# Smart-window_v1_1.net
KiCad netlist of a schematic drawn in EAGLE
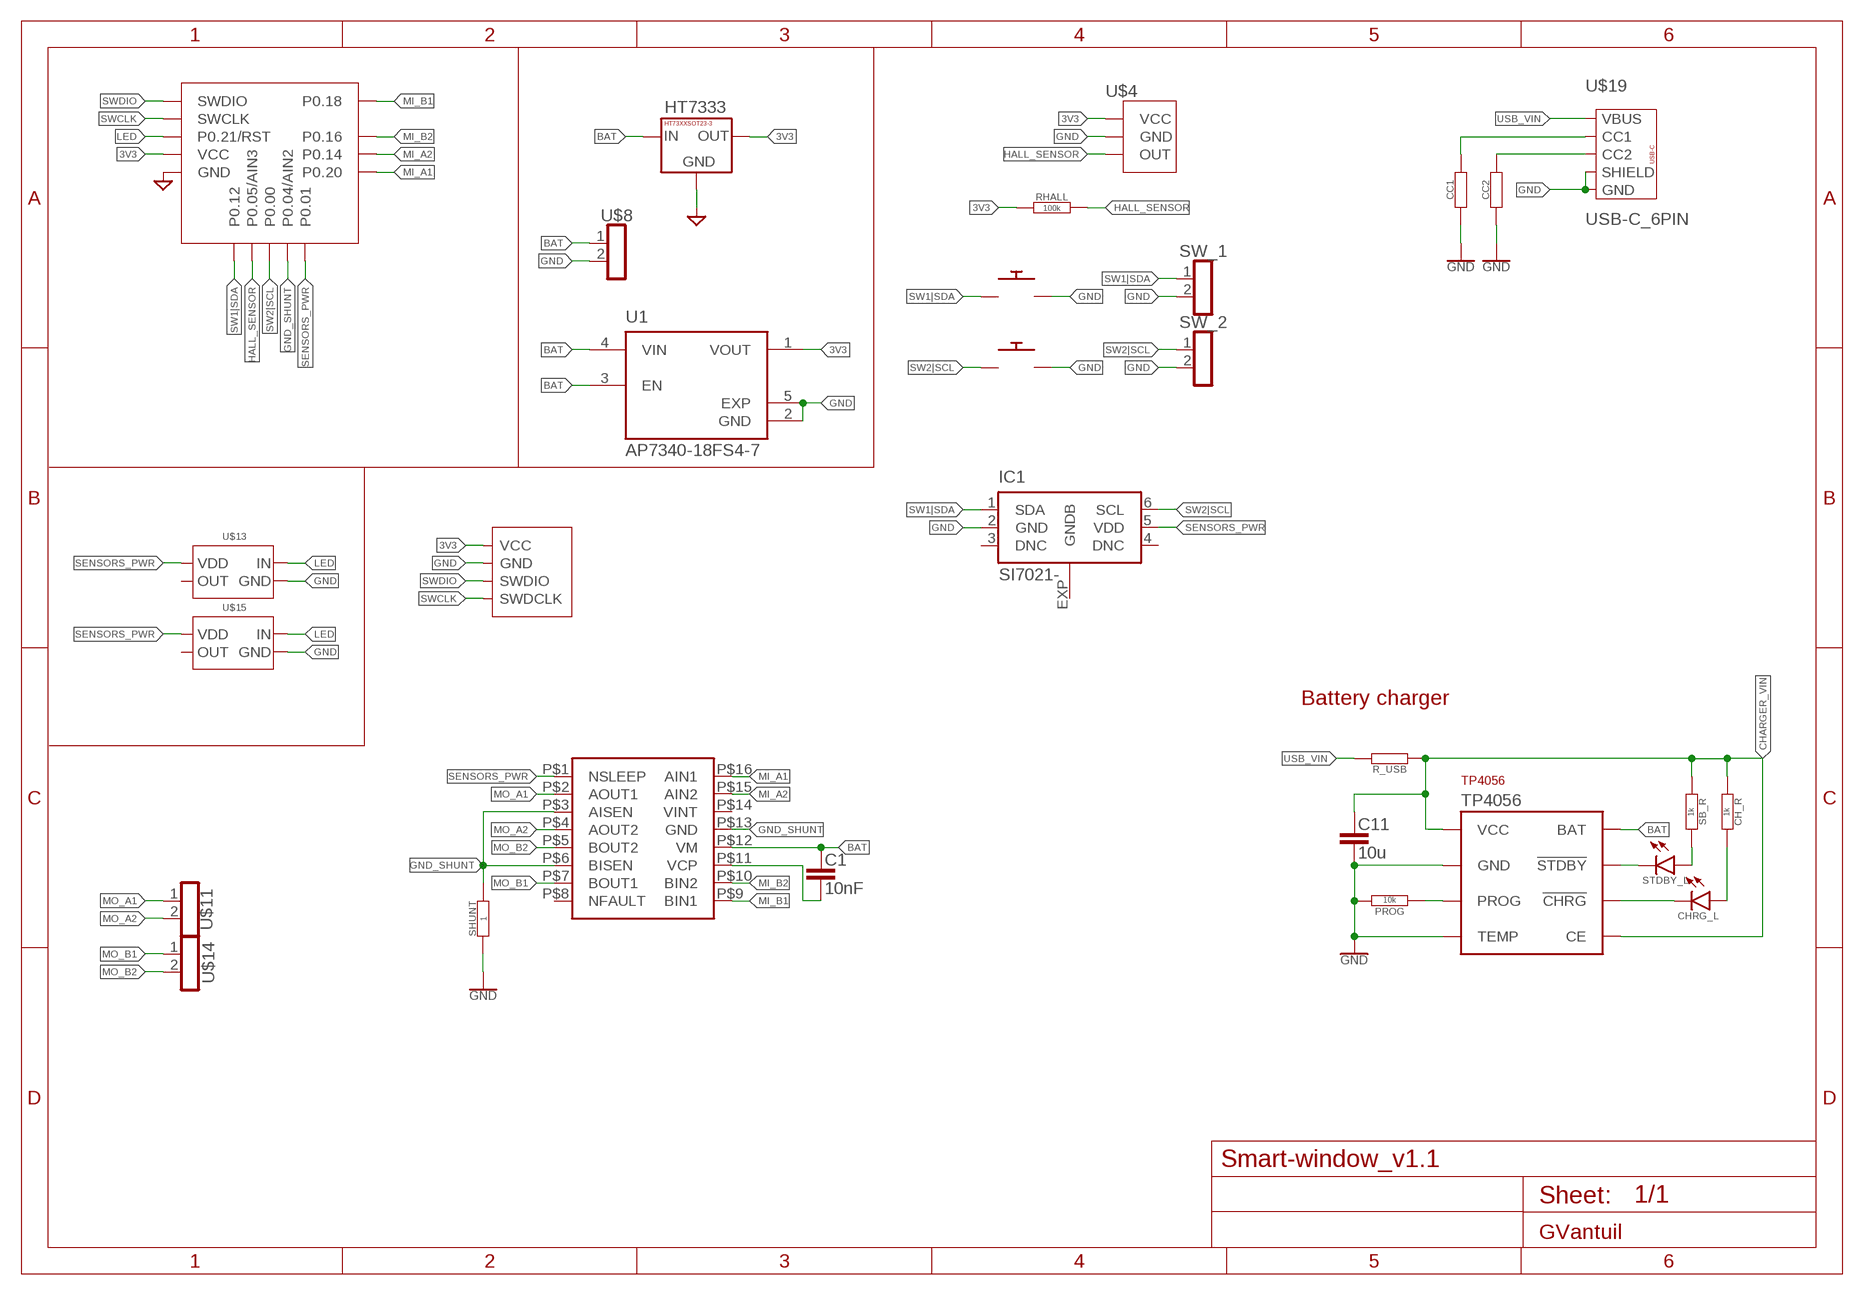
[diagram p0: schematic, sheet 1]

(export (version "E")
  (design (tool "Eeschema 10.0.6"))
  (components
    (comp (ref "C1")
      (value "10nF")
      (footprint "eagle-import:0402-CAP")
      (libsource (lib "eagle-import") (part "CAP_0402-CAP"))
    )
    (comp (ref "C11")
      (value "10u")
      (footprint "eagle-import:0402-CAP")
      (libsource (lib "eagle-import") (part "CAP_0402-CAP"))
    )
    (comp (ref "CC1")
      (value "RESISTOR0402-RES")
      (footprint "eagle-import:0402-RES")
      (libsource (lib "eagle-import") (part "RESISTOR0402-RES"))
    )
    (comp (ref "CC2")
      (value "RESISTOR0402-RES")
      (footprint "eagle-import:0402-RES")
      (libsource (lib "eagle-import") (part "RESISTOR0402-RES"))
    )
    (comp (ref "CHRG_L")
      (value "LED_0402")
      (footprint "eagle-import:0402")
      (libsource (lib "eagle-import") (part "LED_0402"))
    )
    (comp (ref "CH_R")
      (value "1k")
      (footprint "eagle-import:0402-RES")
      (libsource (lib "eagle-import") (part "RESISTOR0402-RES"))
    )
    (comp (ref "HT7333")
      (value "HT73XXSOT23-3")
      (footprint "eagle-import:SOT23-3")
      (libsource (lib "eagle-import") (part "HT73XXSOT23-3"))
    )
    (comp (ref "IC1")
      (value "SI7021-")
      (footprint "eagle-import:DFN6-3X3")
      (libsource (lib "eagle-import") (part "SI7021-"))
    )
    (comp (ref "PROG")
      (value "10k")
      (footprint "eagle-import:0402-RES")
      (libsource (lib "eagle-import") (part "RESISTOR0402-RES"))
    )
    (comp (ref "RHALL")
      (value "100k")
      (footprint "eagle-import:0402-RES")
      (libsource (lib "eagle-import") (part "RESISTOR0402-RES"))
    )
    (comp (ref "R_USB")
      (value "RESISTOR0402-RES")
      (footprint "eagle-import:0402-RES")
      (libsource (lib "eagle-import") (part "RESISTOR0402-RES"))
    )
    (comp (ref "SB_R")
      (value "1k")
      (footprint "eagle-import:0402-RES")
      (libsource (lib "eagle-import") (part "RESISTOR0402-RES"))
    )
    (comp (ref "SHUNT")
      (value "1")
      (footprint "eagle-import:0402-RES")
      (libsource (lib "eagle-import") (part "RESISTOR0402-RES"))
    )
    (comp (ref "STDBY_L")
      (value "LED_0402")
      (footprint "eagle-import:0402")
      (libsource (lib "eagle-import") (part "LED_0402"))
    )
    (comp (ref "SW1")
      (value "PUSHBUTTON_3X3_SMALL_FOOTPRINT")
      (footprint "eagle-import:PUSHBUTTON_3X3MM_(SMALL_FOOTPRINT)")
      (libsource (lib "eagle-import") (part "PUSHBUTTON_3X3_SMALL_FOOTPRINT"))
    )
    (comp (ref "SW2")
      (value "PUSHBUTTON_3X3_SMALL_FOOTPRINT")
      (footprint "eagle-import:PUSHBUTTON_3X3MM_(SMALL_FOOTPRINT)")
      (libsource (lib "eagle-import") (part "PUSHBUTTON_3X3_SMALL_FOOTPRINT"))
    )
    (comp (ref "SW_1")
      (value "PINH1X02_2MM")
      (footprint "eagle-import:1X02_2MM")
      (libsource (lib "eagle-import") (part "PINH1X02_2MM"))
    )
    (comp (ref "SW_2")
      (value "PINH1X02_2MM")
      (footprint "eagle-import:1X02_2MM")
      (libsource (lib "eagle-import") (part "PINH1X02_2MM"))
    )
    (comp (ref "TP4056")
      (value "TP4056_SOP8")
      (footprint "eagle-import:SOP8")
      (libsource (lib "eagle-import") (part "TP4056_SOP8"))
    )
    (comp (ref "U$2")
      (value "E104-BT5005A")
      (footprint "eagle-import:E104-BT5005A")
      (libsource (lib "eagle-import") (part "E104-BT5005A"))
    )
    (comp (ref "U$4")
      (value "49E")
      (footprint "eagle-import:TO92_HALLSENSOR")
      (libsource (lib "eagle-import") (part "49E"))
    )
    (comp (ref "U$8")
      (value "PINH1X02_2MM")
      (footprint "eagle-import:1X02_2MM")
      (libsource (lib "eagle-import") (part "PINH1X02_2MM"))
    )
    (comp (ref "U$9")
      (value "GV_SWD_4P_SEMI_SMD_SMALL_BACK")
      (footprint "eagle-import:GV_SWD_1.27MM_4P_SEMI_SMD_SMALL_BACK")
      (libsource (lib "eagle-import") (part "GV_SWD_4P_SEMI_SMD_SMALL_BACK"))
    )
    (comp (ref "U$11")
      (value "PINH1X02_2MM")
      (footprint "eagle-import:1X02_2MM")
      (libsource (lib "eagle-import") (part "PINH1X02_2MM"))
    )
    (comp (ref "U$12")
      (value "DRV8833_")
      (footprint "eagle-import:SSOP16")
      (libsource (lib "eagle-import") (part "DRV8833_"))
    )
    (comp (ref "U$13")
      (value "SK6805")
      (footprint "eagle-import:LED_ARGB")
      (libsource (lib "eagle-import") (part "SK6805"))
    )
    (comp (ref "U$14")
      (value "PINH1X02_2MM")
      (footprint "eagle-import:1X02_2MM")
      (libsource (lib "eagle-import") (part "PINH1X02_2MM"))
    )
    (comp (ref "U$15")
      (value "SK6805")
      (footprint "eagle-import:LED_ARGB")
      (libsource (lib "eagle-import") (part "SK6805"))
    )
    (comp (ref "U$19")
      (value "USB-C_6PIN")
      (footprint "eagle-import:USCX-06FX-XXMX-01")
      (libsource (lib "eagle-import") (part "USB-C_6PIN"))
    )
    (comp (ref "U1")
      (value "AP7340-18FS4-7")
      (footprint "eagle-import:VREG_AP7340-18FS4-7")
      (fields (field (name "MF") "Diodes Inc."))
      (libsource (lib "eagle-import") (part "AP7340-18FS4-7"))
    )
  )
  (nets
    (net (code "1") (name "3V3") (class "Default")
      (node (ref "HT7333") (pin "2") (pinfunction "3.OUT_2") (pintype "bidirectional"))
      (node (ref "RHALL") (pin "1") (pinfunction "1_1") (pintype "passive"))
      (node (ref "U$2") (pin "VCC") (pinfunction "VCC_VCC") (pintype "bidirectional"))
      (node (ref "U$4") (pin "VCC") (pinfunction "VCC_VCC") (pintype "bidirectional"))
      (node (ref "U$9") (pin "VCC") (pinfunction "VCC_VCC") (pintype "bidirectional"))
      (node (ref "U$9") (pin "VCC1") (pinfunction "VCC_VCC1") (pintype "bidirectional"))
      (node (ref "U1") (pin "1") (pinfunction "VOUT_1") (pintype "output"))
    )
    (net (code "2") (name "BAT") (class "Default")
      (node (ref "C1") (pin "1") (pinfunction "1_1") (pintype "passive"))
      (node (ref "HT7333") (pin "3") (pinfunction "1.IN_3") (pintype "input"))
      (node (ref "TP4056") (pin "P$5") (pinfunction "BAT_P$5") (pintype "bidirectional"))
      (node (ref "U$12") (pin "P$12") (pinfunction "VM_P$12") (pintype "bidirectional"))
      (node (ref "U$8") (pin "1") (pinfunction "1_1") (pintype "passive"))
      (node (ref "U1") (pin "3") (pinfunction "EN_3") (pintype "input"))
      (node (ref "U1") (pin "4") (pinfunction "VIN_4") (pintype "input"))
    )
    (net (code "3") (name "CHARGER_VIN") (class "Default")
      (node (ref "C11") (pin "1") (pinfunction "1_1") (pintype "passive"))
      (node (ref "CH_R") (pin "1") (pinfunction "1_1") (pintype "passive"))
      (node (ref "R_USB") (pin "1") (pinfunction "1_1") (pintype "passive"))
      (node (ref "SB_R") (pin "1") (pinfunction "1_1") (pintype "passive"))
      (node (ref "TP4056") (pin "P$4") (pinfunction "VCC_P$4") (pintype "bidirectional"))
      (node (ref "TP4056") (pin "P$8") (pinfunction "CE_P$8") (pintype "bidirectional"))
    )
    (net (code "4") (name "GND") (class "Default")
      (node (ref "C11") (pin "2") (pinfunction "2_2") (pintype "passive"))
      (node (ref "CC1") (pin "1") (pinfunction "1_1") (pintype "passive"))
      (node (ref "CC2") (pin "1") (pinfunction "1_1") (pintype "passive"))
      (node (ref "HT7333") (pin "1") (pinfunction "2.GND_1") (pintype "input"))
      (node (ref "IC1") (pin "2") (pinfunction "GND_2") (pintype "bidirectional"))
      (node (ref "PROG") (pin "2") (pinfunction "2_2") (pintype "passive"))
      (node (ref "SHUNT") (pin "1") (pinfunction "1_1") (pintype "passive"))
      (node (ref "SW1") (pin "1") (pinfunction "P$1_1") (pintype "bidirectional"))
      (node (ref "SW1") (pin "2") (pinfunction "P$1_2") (pintype "bidirectional"))
      (node (ref "SW2") (pin "1") (pinfunction "P$1_1") (pintype "bidirectional"))
      (node (ref "SW2") (pin "2") (pinfunction "P$1_2") (pintype "bidirectional"))
      (node (ref "SW_1") (pin "2") (pinfunction "2_2") (pintype "passive"))
      (node (ref "SW_2") (pin "2") (pinfunction "2_2") (pintype "passive"))
      (node (ref "TP4056") (pin "P$1") (pinfunction "TEMP_P$1") (pintype "bidirectional"))
      (node (ref "TP4056") (pin "P$3") (pinfunction "GND_P$3") (pintype "bidirectional"))
      (node (ref "U$13") (pin "4") (pinfunction "GND_4") (pintype "bidirectional"))
      (node (ref "U$15") (pin "4") (pinfunction "GND_4") (pintype "bidirectional"))
      (node (ref "U$19") (pin "GND1") (pinfunction "GND_GND1") (pintype "power_in"))
      (node (ref "U$19") (pin "GND2") (pinfunction "GND_GND2") (pintype "power_in"))
      (node (ref "U$19") (pin "SHIELD1") (pinfunction "SHIELD_SHIELD1") (pintype "power_in"))
      (node (ref "U$19") (pin "SHIELD2") (pinfunction "SHIELD_SHIELD2") (pintype "power_in"))
      (node (ref "U$19") (pin "SHIELD3") (pinfunction "SHIELD_SHIELD3") (pintype "power_in"))
      (node (ref "U$19") (pin "SHIELD4") (pinfunction "SHIELD_SHIELD4") (pintype "power_in"))
      (node (ref "U$2") (pin "GND") (pinfunction "GND_GND") (pintype "bidirectional"))
      (node (ref "U$2") (pin "GND1") (pinfunction "GND_GND1") (pintype "bidirectional"))
      (node (ref "U$4") (pin "GND") (pinfunction "GND_GND") (pintype "bidirectional"))
      (node (ref "U$8") (pin "2") (pinfunction "2_2") (pintype "passive"))
      (node (ref "U$9") (pin "GND") (pinfunction "GND_GND") (pintype "bidirectional"))
      (node (ref "U$9") (pin "GND1") (pinfunction "GND_GND1") (pintype "bidirectional"))
      (node (ref "U1") (pin "2") (pinfunction "GND_2") (pintype "power_in"))
      (node (ref "U1") (pin "5") (pinfunction "EXP_5") (pintype "passive"))
    )
    (net (code "5") (name "GND_SHUNT") (class "Default")
      (node (ref "SHUNT") (pin "2") (pinfunction "2_2") (pintype "passive"))
      (node (ref "U$12") (pin "P$13") (pinfunction "GND_P$13") (pintype "bidirectional"))
      (node (ref "U$12") (pin "P$3") (pinfunction "AISEN_P$3") (pintype "bidirectional"))
      (node (ref "U$12") (pin "P$6") (pinfunction "BISEN_P$6") (pintype "bidirectional"))
      (node (ref "U$2") (pin "P0.04") (pinfunction "P0.04/AIN2_P0.04") (pintype "bidirectional"))
    )
    (net (code "6") (name "HALL_SENSOR") (class "Default")
      (node (ref "RHALL") (pin "2") (pinfunction "2_2") (pintype "passive"))
      (node (ref "U$2") (pin "P0.05") (pinfunction "P0.05/AIN3_P0.05") (pintype "bidirectional"))
      (node (ref "U$4") (pin "OUT") (pinfunction "OUT_OUT") (pintype "bidirectional"))
    )
    (net (code "7") (name "LED") (class "Default")
      (node (ref "U$13") (pin "1") (pinfunction "IN_1") (pintype "bidirectional"))
      (node (ref "U$15") (pin "1") (pinfunction "IN_1") (pintype "bidirectional"))
      (node (ref "U$2") (pin "P0.21/RST") (pinfunction "P0.21/RST_P0.21/RST") (pintype "bidirectional"))
    )
    (net (code "8") (name "MI_A1") (class "Default")
      (node (ref "U$12") (pin "P$16") (pinfunction "AIN1_P$16") (pintype "bidirectional"))
      (node (ref "U$2") (pin "P0.20") (pinfunction "P0.20_P0.20") (pintype "bidirectional"))
    )
    (net (code "9") (name "MI_A2") (class "Default")
      (node (ref "U$12") (pin "P$15") (pinfunction "AIN2_P$15") (pintype "bidirectional"))
      (node (ref "U$2") (pin "P0.14") (pinfunction "P0.14_P0.14") (pintype "bidirectional"))
    )
    (net (code "10") (name "MI_B1") (class "Default")
      (node (ref "U$12") (pin "P$9") (pinfunction "BIN1_P$9") (pintype "bidirectional"))
      (node (ref "U$2") (pin "P0.18") (pinfunction "P0.18_P0.18") (pintype "bidirectional"))
    )
    (net (code "11") (name "MI_B2") (class "Default")
      (node (ref "U$12") (pin "P$10") (pinfunction "BIN2_P$10") (pintype "bidirectional"))
      (node (ref "U$2") (pin "P0.16") (pinfunction "P0.16_P0.16") (pintype "bidirectional"))
    )
    (net (code "12") (name "MO_A1") (class "Default")
      (node (ref "U$11") (pin "1") (pinfunction "1_1") (pintype "passive"))
      (node (ref "U$12") (pin "P$2") (pinfunction "AOUT1_P$2") (pintype "bidirectional"))
    )
    (net (code "13") (name "MO_A2") (class "Default")
      (node (ref "U$11") (pin "2") (pinfunction "2_2") (pintype "passive"))
      (node (ref "U$12") (pin "P$4") (pinfunction "AOUT2_P$4") (pintype "bidirectional"))
    )
    (net (code "14") (name "MO_B1") (class "Default")
      (node (ref "U$12") (pin "P$7") (pinfunction "BOUT1_P$7") (pintype "bidirectional"))
      (node (ref "U$14") (pin "1") (pinfunction "1_1") (pintype "passive"))
    )
    (net (code "15") (name "MO_B2") (class "Default")
      (node (ref "U$12") (pin "P$5") (pinfunction "BOUT2_P$5") (pintype "bidirectional"))
      (node (ref "U$14") (pin "2") (pinfunction "2_2") (pintype "passive"))
    )
    (net (code "16") (name "Net-(CC1-Pad2)") (class "Default")
      (node (ref "CC1") (pin "2") (pinfunction "2_2") (pintype "passive"))
      (node (ref "U$19") (pin "CC1") (pinfunction "CC1_CC1") (pintype "bidirectional"))
    )
    (net (code "17") (name "Net-(CC2-Pad2)") (class "Default")
      (node (ref "CC2") (pin "2") (pinfunction "2_2") (pintype "passive"))
      (node (ref "U$19") (pin "CC2") (pinfunction "CC2_CC2") (pintype "bidirectional"))
    )
    (net (code "18") (name "Net-(CHRG_L-PadA)") (class "Default")
      (node (ref "CHRG_L") (pin "A") (pinfunction "A_A") (pintype "passive"))
      (node (ref "CH_R") (pin "2") (pinfunction "2_2") (pintype "passive"))
    )
    (net (code "19") (name "Net-(SB_R-Pad2)") (class "Default")
      (node (ref "SB_R") (pin "2") (pinfunction "2_2") (pintype "passive"))
      (node (ref "STDBY_L") (pin "A") (pinfunction "A_A") (pintype "passive"))
    )
    (net (code "20") (name "Net-(TP4056-PROG)") (class "Default")
      (node (ref "PROG") (pin "1") (pinfunction "1_1") (pintype "passive"))
      (node (ref "TP4056") (pin "P$2") (pinfunction "PROG_P$2") (pintype "bidirectional"))
    )
    (net (code "21") (name "Net-(TP4056-~{CHRG})") (class "Default")
      (node (ref "CHRG_L") (pin "C") (pinfunction "C_C") (pintype "passive"))
      (node (ref "TP4056") (pin "P$7") (pinfunction "~{CHRG}_P$7") (pintype "bidirectional"))
    )
    (net (code "22") (name "Net-(TP4056-~{STDBY})") (class "Default")
      (node (ref "STDBY_L") (pin "C") (pinfunction "C_C") (pintype "passive"))
      (node (ref "TP4056") (pin "P$6") (pinfunction "~{STDBY}_P$6") (pintype "bidirectional"))
    )
    (net (code "23") (name "Net-(U$12-VCP)") (class "Default")
      (node (ref "C1") (pin "2") (pinfunction "2_2") (pintype "passive"))
      (node (ref "U$12") (pin "P$11") (pinfunction "VCP_P$11") (pintype "bidirectional"))
    )
    (net (code "24") (name "SENSORS_PWR") (class "Default")
      (node (ref "IC1") (pin "5") (pinfunction "VDD_5") (pintype "bidirectional"))
      (node (ref "U$12") (pin "P$1") (pinfunction "NSLEEP_P$1") (pintype "bidirectional"))
      (node (ref "U$13") (pin "2") (pinfunction "VDD_2") (pintype "bidirectional"))
      (node (ref "U$15") (pin "2") (pinfunction "VDD_2") (pintype "bidirectional"))
      (node (ref "U$2") (pin "P0.01") (pinfunction "P0.01_P0.01") (pintype "bidirectional"))
    )
    (net (code "25") (name "SW1|SDA") (class "Default")
      (node (ref "IC1") (pin "1") (pinfunction "SDA_1") (pintype "bidirectional"))
      (node (ref "SW1") (pin "3") (pinfunction "P$2_3") (pintype "bidirectional"))
      (node (ref "SW1") (pin "4") (pinfunction "P$2_4") (pintype "bidirectional"))
      (node (ref "SW_1") (pin "1") (pinfunction "1_1") (pintype "passive"))
      (node (ref "U$2") (pin "P0.12") (pinfunction "P0.12_P0.12") (pintype "bidirectional"))
    )
    (net (code "26") (name "SW2|SCL") (class "Default")
      (node (ref "IC1") (pin "6") (pinfunction "SCL_6") (pintype "input"))
      (node (ref "SW2") (pin "3") (pinfunction "P$2_3") (pintype "bidirectional"))
      (node (ref "SW2") (pin "4") (pinfunction "P$2_4") (pintype "bidirectional"))
      (node (ref "SW_2") (pin "1") (pinfunction "1_1") (pintype "passive"))
      (node (ref "U$2") (pin "P0.00") (pinfunction "P0.00_P0.00") (pintype "bidirectional"))
    )
    (net (code "27") (name "SWCLK") (class "Default")
      (node (ref "U$2") (pin "SWCLK") (pinfunction "SWCLK_SWCLK") (pintype "bidirectional"))
      (node (ref "U$9") (pin "SWDCLK") (pinfunction "SWDCLK_SWDCLK") (pintype "bidirectional"))
    )
    (net (code "28") (name "SWDIO") (class "Default")
      (node (ref "U$2") (pin "SWDIO") (pinfunction "SWDIO_SWDIO") (pintype "bidirectional"))
      (node (ref "U$9") (pin "SWDIO") (pinfunction "SWDIO_SWDIO") (pintype "bidirectional"))
    )
    (net (code "29") (name "USB_VIN") (class "Default")
      (node (ref "R_USB") (pin "2") (pinfunction "2_2") (pintype "passive"))
      (node (ref "U$19") (pin "VBUS1") (pinfunction "VBUS_VBUS1") (pintype "power_in"))
      (node (ref "U$19") (pin "VBUS2") (pinfunction "VBUS_VBUS2") (pintype "power_in"))
    )
    (net (code "30") (name "unconnected-(IC1-DNC-Pad3)") (class "Default")
      (node (ref "IC1") (pin "3") (pinfunction "DNC_3") (pintype "no_connect"))
    )
    (net (code "31") (name "unconnected-(IC1-DNC-Pad4)") (class "Default")
      (node (ref "IC1") (pin "4") (pinfunction "DNC_4") (pintype "no_connect"))
    )
    (net (code "32") (name "unconnected-(IC1-GNDB-PadEXP)") (class "Default")
      (node (ref "IC1") (pin "EXP") (pinfunction "GNDB_EXP") (pintype "bidirectional"))
    )
    (net (code "33") (name "unconnected-(U$12-NFAULT-PadP$8)") (class "Default")
      (node (ref "U$12") (pin "P$8") (pinfunction "NFAULT_P$8") (pintype "bidirectional"))
    )
    (net (code "34") (name "unconnected-(U$12-VINT-PadP$14)") (class "Default")
      (node (ref "U$12") (pin "P$14") (pinfunction "VINT_P$14") (pintype "bidirectional"))
    )
    (net (code "35") (name "unconnected-(U$13-OUT-Pad3)") (class "Default")
      (node (ref "U$13") (pin "3") (pinfunction "OUT_3") (pintype "bidirectional"))
    )
    (net (code "36") (name "unconnected-(U$15-OUT-Pad3)") (class "Default")
      (node (ref "U$15") (pin "3") (pinfunction "OUT_3") (pintype "bidirectional"))
    )
  )
)
